# quad-hybrid-QCN-xxx.net
KiCad netlist of a schematic drawn in EAGLE
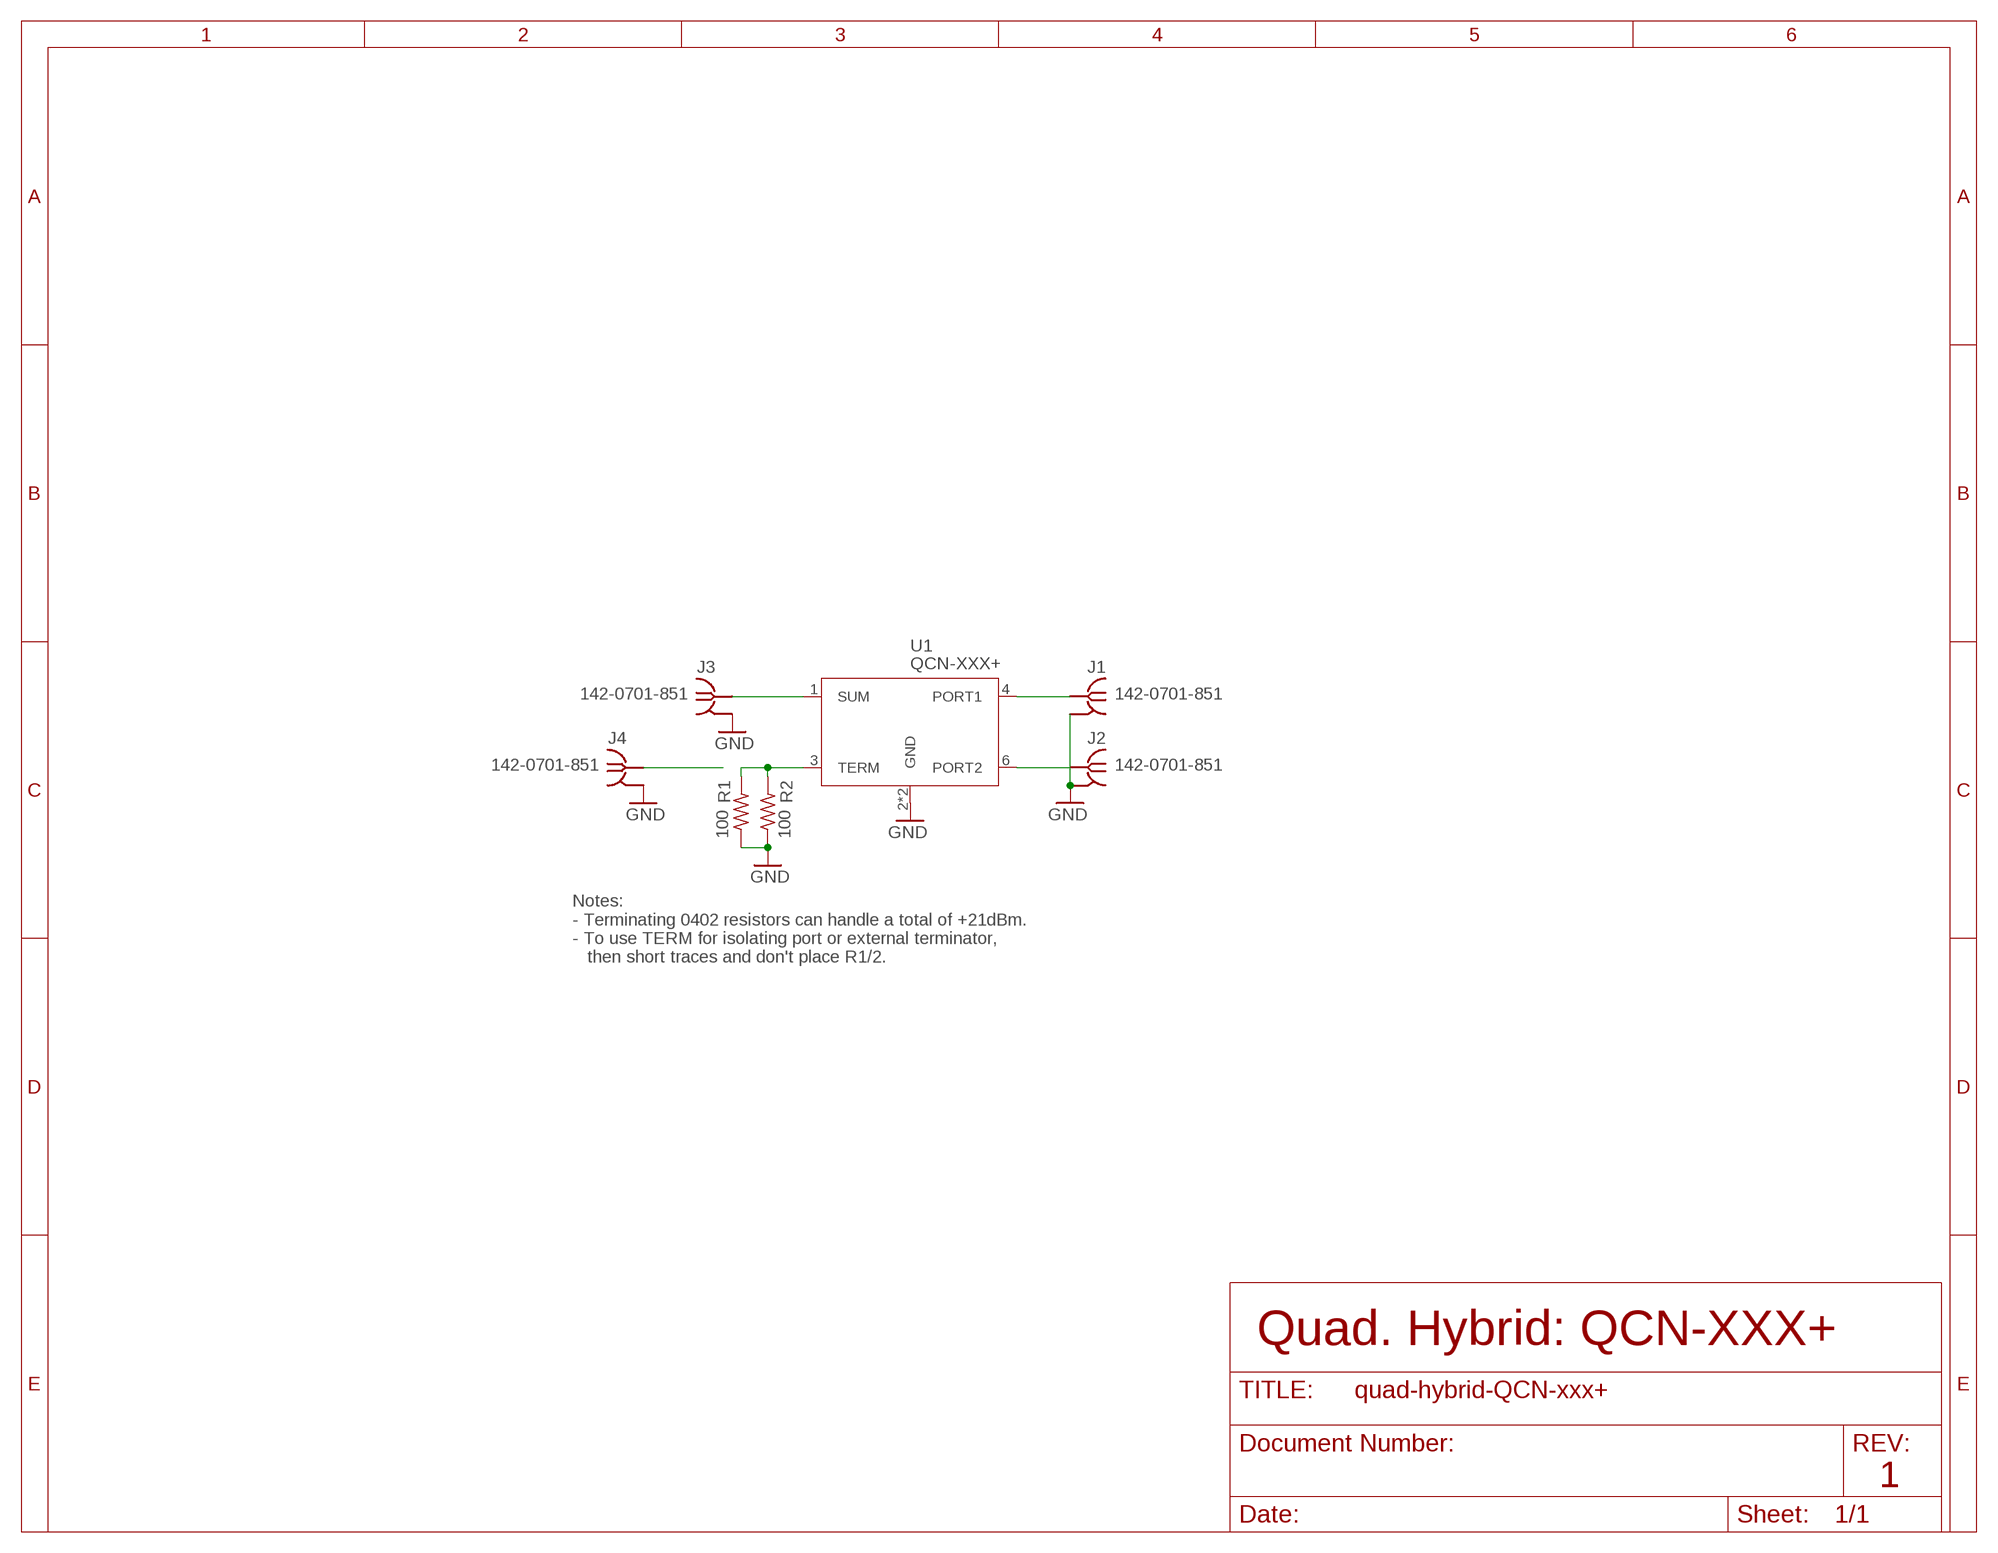
[diagram p0: schematic, sheet 1]

(export (version "E")
  (design (tool "Eeschema 10.0.6"))
  (components
    (comp (ref "J1")
      (value "142-0701-851")
      (footprint "eagle-import:142-0701-851")
      (libsource (lib "eagle-import") (part "142-0701-851"))
    )
    (comp (ref "J2")
      (value "142-0701-851")
      (footprint "eagle-import:142-0701-851")
      (libsource (lib "eagle-import") (part "142-0701-851"))
    )
    (comp (ref "J3")
      (value "142-0701-851")
      (footprint "eagle-import:142-0701-851")
      (libsource (lib "eagle-import") (part "142-0701-851"))
    )
    (comp (ref "J4")
      (value "142-0701-851")
      (footprint "eagle-import:142-0701-851")
      (libsource (lib "eagle-import") (part "142-0701-851"))
    )
    (comp (ref "R1")
      (value "100")
      (footprint "eagle-import:.0402-C-NOSILK")
      (libsource (lib "eagle-import") (part "R-US_0402-C-NOSILK"))
    )
    (comp (ref "R2")
      (value "100")
      (footprint "eagle-import:.0402-C-NOSILK")
      (libsource (lib "eagle-import") (part "R-US_0402-C-NOSILK"))
    )
    (comp (ref "U1")
      (value "QCN-XXX+")
      (footprint "eagle-import:QCN-XXX+")
      (libsource (lib "eagle-import") (part "QCN-XXX+"))
    )
  )
  (nets
    (net (code "1") (name "GND") (class "Default")
      (node (ref "J1") (pin "GND1") (pinfunction "GND_GND1") (pintype "bidirectional"))
      (node (ref "J1") (pin "GND2") (pinfunction "GND_GND2") (pintype "bidirectional"))
      (node (ref "J1") (pin "GND3") (pinfunction "GND_GND3") (pintype "bidirectional"))
      (node (ref "J1") (pin "GND4") (pinfunction "GND_GND4") (pintype "bidirectional"))
      (node (ref "J2") (pin "GND1") (pinfunction "GND_GND1") (pintype "bidirectional"))
      (node (ref "J2") (pin "GND2") (pinfunction "GND_GND2") (pintype "bidirectional"))
      (node (ref "J2") (pin "GND3") (pinfunction "GND_GND3") (pintype "bidirectional"))
      (node (ref "J2") (pin "GND4") (pinfunction "GND_GND4") (pintype "bidirectional"))
      (node (ref "J3") (pin "GND1") (pinfunction "GND_GND1") (pintype "bidirectional"))
      (node (ref "J3") (pin "GND2") (pinfunction "GND_GND2") (pintype "bidirectional"))
      (node (ref "J3") (pin "GND3") (pinfunction "GND_GND3") (pintype "bidirectional"))
      (node (ref "J3") (pin "GND4") (pinfunction "GND_GND4") (pintype "bidirectional"))
      (node (ref "J4") (pin "GND1") (pinfunction "GND_GND1") (pintype "bidirectional"))
      (node (ref "J4") (pin "GND2") (pinfunction "GND_GND2") (pintype "bidirectional"))
      (node (ref "J4") (pin "GND3") (pinfunction "GND_GND3") (pintype "bidirectional"))
      (node (ref "J4") (pin "GND4") (pinfunction "GND_GND4") (pintype "bidirectional"))
      (node (ref "R1") (pin "1") (pinfunction "1_1") (pintype "passive"))
      (node (ref "R2") (pin "1") (pinfunction "1_1") (pintype "passive"))
      (node (ref "U1") (pin "2") (pinfunction "GND_2") (pintype "power_in"))
      (node (ref "U1") (pin "5") (pinfunction "GND_5") (pintype "power_in"))
    )
    (net (code "2") (name "Net-(J1-RF)") (class "Default")
      (node (ref "J1") (pin "RF1") (pinfunction "RF_RF1") (pintype "bidirectional"))
      (node (ref "U1") (pin "4") (pinfunction "PORT1_4") (pintype "bidirectional"))
    )
    (net (code "3") (name "Net-(J2-RF)") (class "Default")
      (node (ref "J2") (pin "RF1") (pinfunction "RF_RF1") (pintype "bidirectional"))
      (node (ref "U1") (pin "6") (pinfunction "PORT2_6") (pintype "bidirectional"))
    )
    (net (code "4") (name "Net-(J3-RF)") (class "Default")
      (node (ref "J3") (pin "RF1") (pinfunction "RF_RF1") (pintype "bidirectional"))
      (node (ref "U1") (pin "1") (pinfunction "SUM_1") (pintype "bidirectional"))
    )
    (net (code "5") (name "Net-(U1-TERM)") (class "Default")
      (node (ref "R1") (pin "2") (pinfunction "2_2") (pintype "passive"))
      (node (ref "R2") (pin "2") (pinfunction "2_2") (pintype "passive"))
      (node (ref "U1") (pin "3") (pinfunction "TERM_3") (pintype "bidirectional"))
    )
    (net (code "6") (name "unconnected-(J4-RF-PadRF1)") (class "Default")
      (node (ref "J4") (pin "RF1") (pinfunction "RF_RF1") (pintype "bidirectional"))
    )
  )
)
